# GPS_Adapter.net
KiCad netlist of a schematic drawn in Altium Designer
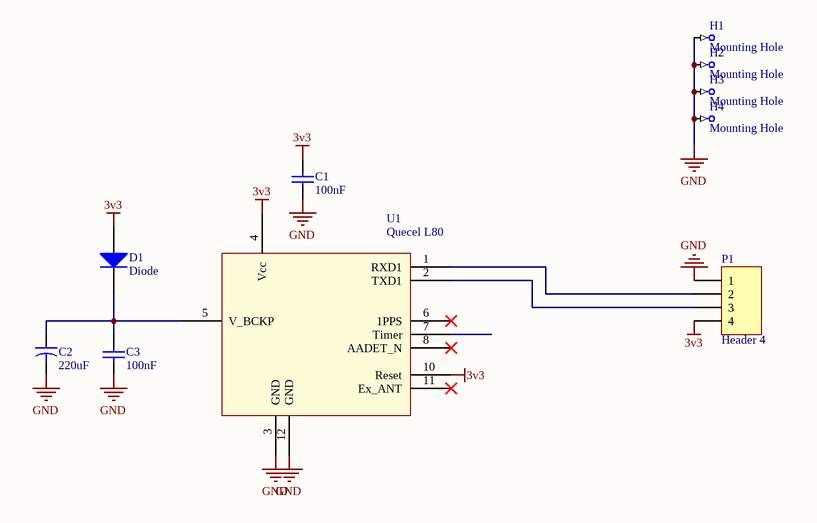
[diagram p0: GPS_Adapter.SchDoc]

(export (version "E")
  (design (tool "Eeschema 10.0.6"))
  (components
    (comp (ref "C1")
      (value "100nF")
      (footprint "R0805")
      (description "Capacitor")
      (fields (field (name "PUBLISHER") "Altium Limited"))
      (libsource (lib "Miscellaneous Devices") (part "Cap"))
    )
    (comp (ref "C2")
      (value "220uF")
      (footprint "SMD CAPACITOR 220UF 16V")
      (description "Capacitor")
      (fields (field (name "PUBLISHER") "Altium Limited"))
      (libsource (lib "Miscellaneous Devices") (part "Cap2"))
    )
    (comp (ref "C3")
      (value "100nF")
      (footprint "R0805")
      (description "Capacitor")
      (fields (field (name "PUBLISHER") "Altium Limited"))
      (libsource (lib "Miscellaneous Devices") (part "Cap"))
    )
    (comp (ref "D1")
      (value "Diode")
      (footprint "Diode")
      (description "Default Diode")
      (fields (field (name "PUBLISHER") "Altium Limited"))
      (libsource (lib "Miscellaneous Devices") (part "Diode"))
    )
    (comp (ref "H1")
      (value "Mounting Hole")
      (footprint "M3 BOLT HOLE")
      (libsource (lib "SpiritLevel_2E") (part "TestPin"))
    )
    (comp (ref "H2")
      (value "Mounting Hole")
      (footprint "M3 BOLT HOLE")
      (libsource (lib "SpiritLevel_2E") (part "TestPin"))
    )
    (comp (ref "H3")
      (value "Mounting Hole")
      (footprint "M3 BOLT HOLE")
      (libsource (lib "SpiritLevel_2E") (part "TestPin"))
    )
    (comp (ref "H4")
      (value "Mounting Hole")
      (footprint "M3 BOLT HOLE")
      (libsource (lib "SpiritLevel_2E") (part "TestPin"))
    )
    (comp (ref "P1")
      (value "Header 4")
      (footprint "SMD 4Wire")
      (description "Header, 4-Pin")
      (fields (field (name "PUBLISHER") "Altium Limited"))
      (libsource (lib "Miscellaneous Connectors") (part "Header 4"))
    )
    (comp (ref "U1")
      (value "Quecel L80")
      (footprint "Quectel L80 GPS")
      (libsource (lib "MiscModules1") (part "Quecel L80"))
    )
  )
  (nets
    (net (code "1") (name "3v3") (class "Default")
      (node (ref "C1") (pin "2") (pinfunction "2_2") (pintype "passive"))
      (node (ref "D1") (pin "1") (pinfunction "A_1") (pintype "passive"))
      (node (ref "P1") (pin "4") (pinfunction "4_4") (pintype "passive"))
      (node (ref "U1") (pin "10") (pinfunction "Reset_10") (pintype "passive"))
      (node (ref "U1") (pin "4") (pinfunction "Vcc_4") (pintype "passive"))
    )
    (net (code "2") (name "GND") (class "Default")
      (node (ref "C1") (pin "1") (pinfunction "1_1") (pintype "passive"))
      (node (ref "C2") (pin "2") (pinfunction "2_2") (pintype "passive"))
      (node (ref "C3") (pin "1") (pinfunction "1_1") (pintype "passive"))
      (node (ref "H1") (pin "1") (pinfunction "1_1") (pintype "input"))
      (node (ref "H2") (pin "1") (pinfunction "1_1") (pintype "input"))
      (node (ref "H3") (pin "1") (pinfunction "1_1") (pintype "input"))
      (node (ref "H4") (pin "1") (pinfunction "1_1") (pintype "input"))
      (node (ref "P1") (pin "1") (pinfunction "1_1") (pintype "passive"))
      (node (ref "U1") (pin "12") (pinfunction "GND_12") (pintype "passive"))
      (node (ref "U1") (pin "3") (pinfunction "GND_3") (pintype "passive"))
    )
    (net (code "3") (name "Net-(D1-K)") (class "Default")
      (node (ref "C2") (pin "1") (pinfunction "1_1") (pintype "passive"))
      (node (ref "C3") (pin "2") (pinfunction "2_2") (pintype "passive"))
      (node (ref "D1") (pin "2") (pinfunction "K_2") (pintype "passive"))
      (node (ref "U1") (pin "5") (pinfunction "V_BCKP_5") (pintype "passive"))
    )
    (net (code "4") (name "Net-(U1-RXD1)") (class "Default")
      (node (ref "P1") (pin "2") (pinfunction "2_2") (pintype "passive"))
      (node (ref "U1") (pin "1") (pinfunction "RXD1_1") (pintype "passive"))
    )
    (net (code "5") (name "Net-(U1-TXD1)") (class "Default")
      (node (ref "P1") (pin "3") (pinfunction "3_3") (pintype "passive"))
      (node (ref "U1") (pin "2") (pinfunction "TXD1_2") (pintype "passive"))
    )
    (net (code "6") (name "unconnected-(U1-1PPS-Pad6)") (class "Default")
      (node (ref "U1") (pin "6") (pinfunction "1PPS_6") (pintype "passive+no_connect"))
    )
    (net (code "7") (name "unconnected-(U1-AADET_N-Pad8)") (class "Default")
      (node (ref "U1") (pin "8") (pinfunction "AADET_N_8") (pintype "passive+no_connect"))
    )
    (net (code "8") (name "unconnected-(U1-Ex_ANT-Pad11)") (class "Default")
      (node (ref "U1") (pin "11") (pinfunction "Ex_ANT_11") (pintype "passive+no_connect"))
    )
    (net (code "9") (name "unconnected-(U1-Timer-Pad7)") (class "Default")
      (node (ref "U1") (pin "7") (pinfunction "Timer_7") (pintype "passive"))
    )
  )
)
